# Interface.net
KiCad netlist of a schematic drawn in Altium Designer
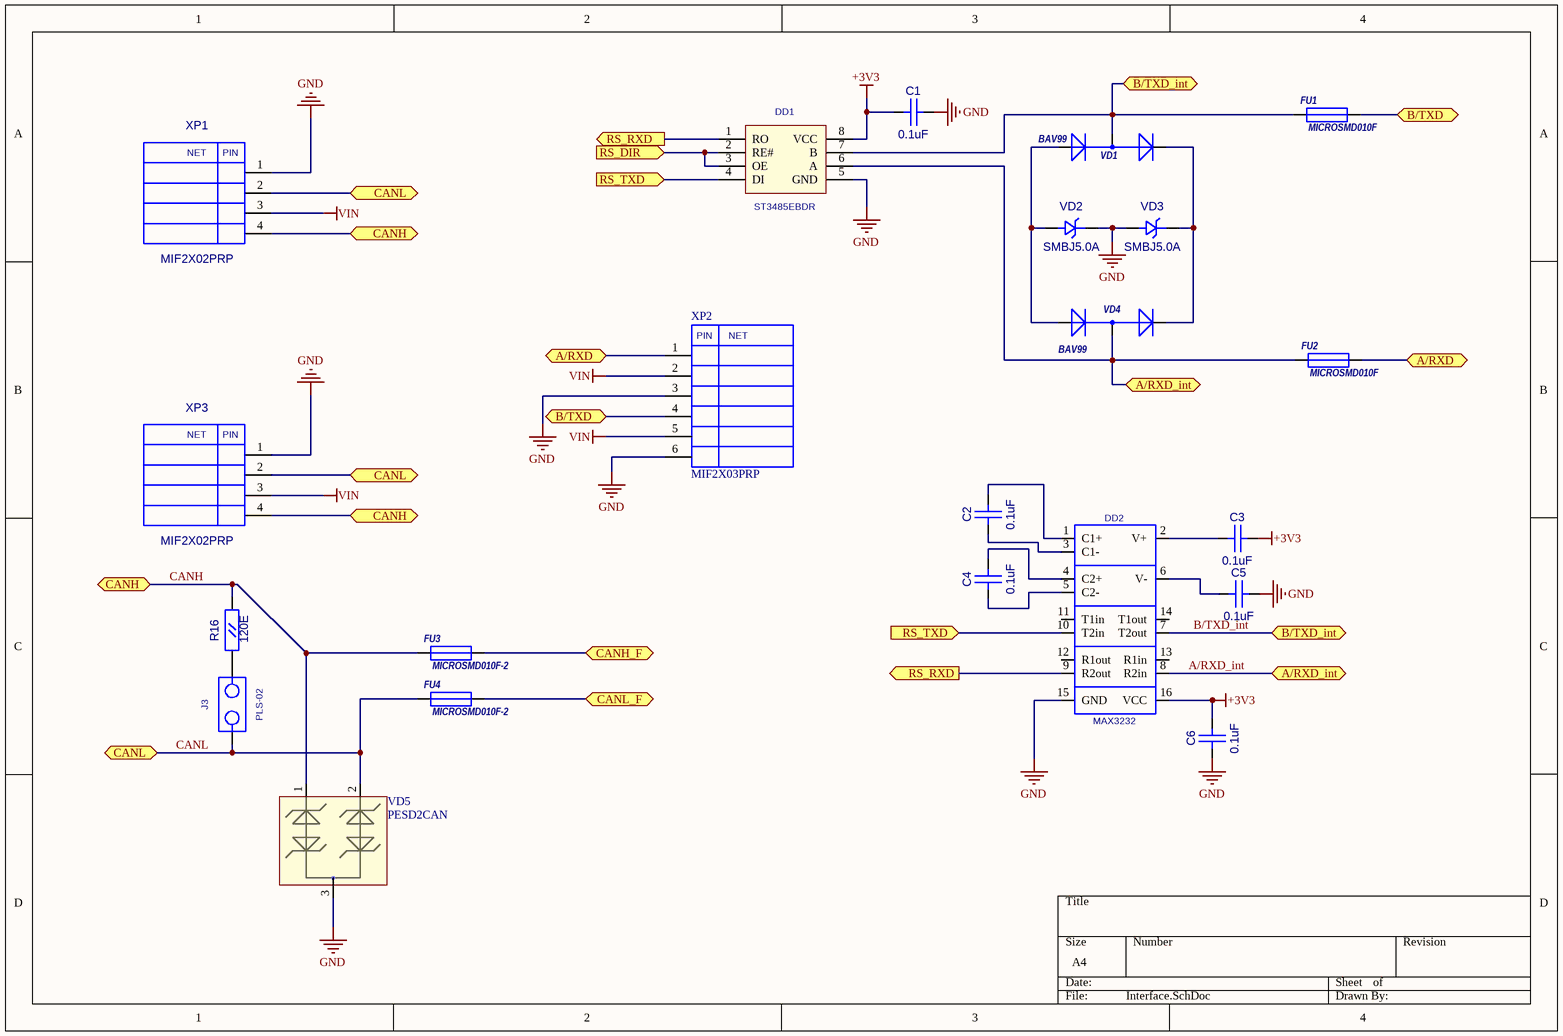
[diagram p0: Interface.SchDoc]

(export (version "E")
  (design (tool "Eeschema 10.0.6"))
  (components
    (comp (ref "C1")
      (value "0.1uF")
      (footprint "CC0603")
      (description "CC0603")
      (libsource (lib "gprs_modem_2") (part "CC0603"))
    )
    (comp (ref "C2")
      (value "0.1uF")
      (footprint "CC0603")
      (description "CC0603")
      (libsource (lib "gprs_modem_2") (part "CC0603"))
    )
    (comp (ref "C3")
      (value "0.1uF")
      (footprint "CC0603")
      (description "CC0603")
      (libsource (lib "gprs_modem_2") (part "CC0603"))
    )
    (comp (ref "C4")
      (value "0.1uF")
      (footprint "CC0603")
      (description "CC0603")
      (libsource (lib "gprs_modem_2") (part "CC0603"))
    )
    (comp (ref "C5")
      (value "0.1uF")
      (footprint "CC0603")
      (description "CC0603")
      (libsource (lib "gprs_modem_2") (part "CC0603"))
    )
    (comp (ref "C6")
      (value "0.1uF")
      (footprint "CC0603")
      (description "CC0603")
      (libsource (lib "gprs_modem_2") (part "CC0603"))
    )
    (comp (ref "DD1")
      (value "ST3485EBDR")
      (footprint "SO-8")
      (description "SP485")
      (libsource (lib "gprs_modem_2") (part "SP485"))
    )
    (comp (ref "DD2")
      (value "MAX3232")
      (footprint "SO16_M")
      (description "ST232BD/CD")
      (libsource (lib "gprs_modem_2") (part "ST232BD/CD"))
    )
    (comp (ref "FU1")
      (value "MICROSMD010F")
      (footprint "RC1210")
      (description "MICROSMD")
      (libsource (lib "gprs_modem_2") (part "MICROSMD"))
    )
    (comp (ref "FU2")
      (value "MICROSMD010F")
      (footprint "RC1210")
      (description "MICROSMD")
      (libsource (lib "gprs_modem_2") (part "MICROSMD"))
    )
    (comp (ref "FU3")
      (value "MICROSMD010F-2")
      (footprint "RC1210")
      (description "MICROSMD")
      (libsource (lib "gprs_modem_2") (part "MICROSMD"))
    )
    (comp (ref "FU4")
      (value "MICROSMD010F-2")
      (footprint "RC1210")
      (description "MICROSMD")
      (libsource (lib "gprs_modem_2") (part "MICROSMD"))
    )
    (comp (ref "J3") (value "PLS-02") (footprint "PLS-02") (libsource (lib "gprs_modem_2") (part "PLS-02")))
    (comp (ref "R16")
      (value "120E")
      (footprint "RC0805")
      (description "RC0805")
      (libsource (lib "gprs_modem_2") (part "RC0805"))
    )
    (comp (ref "VD1")
      (value "BAV99")
      (footprint "SOT-23(GSD)")
      (description "1.0 Ampere General Purpose Rectifier")
      (libsource (lib "gprs_modem_2") (part "BAV99"))
    )
    (comp (ref "VD2")
      (value "SMBJ5.0A")
      (footprint "SMB")
      (description "SMBJ")
      (libsource (lib "gprs_modem_2") (part "SMBJ"))
    )
    (comp (ref "VD3")
      (value "SMBJ5.0A")
      (footprint "SMB")
      (description "SMBJ")
      (libsource (lib "gprs_modem_2") (part "SMBJ"))
    )
    (comp (ref "VD4")
      (value "BAV99")
      (footprint "SOT-23(GSD)")
      (description "1.0 Ampere General Purpose Rectifier")
      (libsource (lib "gprs_modem_2") (part "BAV99"))
    )
    (comp (ref "VD5")
      (value "PESD2CAN")
      (footprint "SOT-23(123)")
      (description "TVS for CAN")
      (libsource (lib "gprs_modem_2") (part "PESD2CAN"))
    )
    (comp (ref "XP1")
      (value "MIF2X02PRP")
      (footprint "MIF2X02PRP")
      (libsource (lib "gprs_modem_2") (part "MIF2X02PRP"))
    )
    (comp (ref "XP2")
      (value "MIF2X03PRP")
      (footprint "MIF2X03PRP")
      (description "MIF2x03PRP")
      (libsource (lib "gprs_modem") (part "MIF2X03PRP"))
    )
    (comp (ref "XP3")
      (value "MIF2X02PRP")
      (footprint "MIF2X02PRP")
      (libsource (lib "gprs_modem_2") (part "MIF2X02PRP"))
    )
  )
  (nets
    (net (code "1") (name "+3V3") (class "Default")
      (node (ref "C1") (pin "1") (pinfunction "A_1") (pintype "passive"))
      (node (ref "C3") (pin "2") (pinfunction "B_2") (pintype "passive"))
      (node (ref "C6") (pin "2") (pinfunction "B_2") (pintype "passive"))
      (node (ref "DD1") (pin "8") (pinfunction "VCC_8") (pintype "passive"))
      (node (ref "DD2") (pin "16") (pinfunction "VCC_16") (pintype "passive"))
    )
    (net (code "2") (name "/A{slash}RXD") (class "Default")
      (node (ref "FU2") (pin "2") (pintype "passive"))
      (node (ref "XP2") (pin "1") (pinfunction "1_1") (pintype "passive"))
    )
    (net (code "3") (name "/A{slash}RXD_int") (class "Default")
      (node (ref "DD1") (pin "6") (pinfunction "A_6") (pintype "passive"))
      (node (ref "DD2") (pin "8") (pinfunction "R2in_8") (pintype "passive"))
      (node (ref "FU2") (pin "1") (pintype "passive"))
      (node (ref "VD4") (pin "3") (pinfunction "AK_3") (pintype "passive"))
    )
    (net (code "4") (name "/B{slash}TXD") (class "Default")
      (node (ref "FU1") (pin "2") (pintype "passive"))
      (node (ref "XP2") (pin "4") (pinfunction "4_4") (pintype "passive"))
    )
    (net (code "5") (name "/B{slash}TXD_int") (class "Default")
      (node (ref "DD1") (pin "7") (pinfunction "B_7") (pintype "passive"))
      (node (ref "DD2") (pin "7") (pinfunction "T2out_7") (pintype "passive"))
      (node (ref "FU1") (pin "1") (pintype "passive"))
      (node (ref "VD1") (pin "3") (pinfunction "AK_3") (pintype "passive"))
    )
    (net (code "6") (name "/CANH") (class "Default")
      (node (ref "FU3") (pin "1") (pintype "passive"))
      (node (ref "R16") (pin "2") (pinfunction "B_2") (pintype "passive"))
      (node (ref "VD5") (pin "1") (pinfunction "1_1") (pintype "passive"))
      (node (ref "XP1") (pin "4") (pinfunction "4_4") (pintype "passive"))
      (node (ref "XP3") (pin "4") (pinfunction "4_4") (pintype "passive"))
    )
    (net (code "7") (name "/CANH_F") (class "Default") (node (ref "FU3") (pin "2") (pintype "passive")))
    (net (code "8") (name "/CANL") (class "Default")
      (node (ref "FU4") (pin "1") (pintype "passive"))
      (node (ref "J3") (pin "1") (pintype "passive"))
      (node (ref "VD5") (pin "2") (pinfunction "2_2") (pintype "passive"))
      (node (ref "XP1") (pin "2") (pinfunction "2_2") (pintype "passive"))
      (node (ref "XP3") (pin "2") (pinfunction "2_2") (pintype "passive"))
    )
    (net (code "9") (name "/CANL_F") (class "Default") (node (ref "FU4") (pin "2") (pintype "passive")))
    (net (code "10") (name "/RS_DIR") (class "Default")
      (node (ref "DD1") (pin "2") (pinfunction "RE#_2") (pintype "passive"))
      (node (ref "DD1") (pin "3") (pinfunction "OE_3") (pintype "passive"))
    )
    (net (code "11") (name "/RS_RXD") (class "Default")
      (node (ref "DD1") (pin "1") (pinfunction "RO_1") (pintype "passive"))
      (node (ref "DD2") (pin "9") (pinfunction "R2out_9") (pintype "passive"))
    )
    (net (code "12") (name "/RS_TXD") (class "Default")
      (node (ref "DD1") (pin "4") (pinfunction "DI_4") (pintype "passive"))
      (node (ref "DD2") (pin "10") (pinfunction "T2in_10") (pintype "passive"))
    )
    (net (code "13") (name "GND") (class "Default")
      (node (ref "C1") (pin "2") (pinfunction "B_2") (pintype "passive"))
      (node (ref "C5") (pin "2") (pinfunction "B_2") (pintype "passive"))
      (node (ref "C6") (pin "1") (pinfunction "A_1") (pintype "passive"))
      (node (ref "DD1") (pin "5") (pinfunction "GND_5") (pintype "passive"))
      (node (ref "DD2") (pin "15") (pinfunction "GND_15") (pintype "passive"))
      (node (ref "VD2") (pin "2") (pinfunction "K_2") (pintype "passive"))
      (node (ref "VD3") (pin "1") (pinfunction "A_1") (pintype "passive"))
      (node (ref "VD5") (pin "3") (pinfunction "3_3") (pintype "passive"))
      (node (ref "XP1") (pin "1") (pinfunction "1_1") (pintype "passive"))
      (node (ref "XP2") (pin "3") (pinfunction "3_3") (pintype "passive"))
      (node (ref "XP2") (pin "6") (pinfunction "6_6") (pintype "passive"))
      (node (ref "XP3") (pin "1") (pinfunction "1_1") (pintype "passive"))
    )
    (net (code "14") (name "Net-(C2-A)") (class "Default")
      (node (ref "C2") (pin "1") (pinfunction "A_1") (pintype "passive"))
      (node (ref "DD2") (pin "3") (pinfunction "C1-_3") (pintype "passive"))
    )
    (net (code "15") (name "Net-(C2-B)") (class "Default")
      (node (ref "C2") (pin "2") (pinfunction "B_2") (pintype "passive"))
      (node (ref "DD2") (pin "1") (pinfunction "C1+_1") (pintype "passive"))
    )
    (net (code "16") (name "Net-(C3-A)") (class "Default")
      (node (ref "C3") (pin "1") (pinfunction "A_1") (pintype "passive"))
      (node (ref "DD2") (pin "2") (pinfunction "V+_2") (pintype "passive"))
    )
    (net (code "17") (name "Net-(C4-A)") (class "Default")
      (node (ref "C4") (pin "1") (pinfunction "A_1") (pintype "passive"))
      (node (ref "DD2") (pin "5") (pinfunction "C2-_5") (pintype "passive"))
    )
    (net (code "18") (name "Net-(C4-B)") (class "Default")
      (node (ref "C4") (pin "2") (pinfunction "B_2") (pintype "passive"))
      (node (ref "DD2") (pin "4") (pinfunction "C2+_4") (pintype "passive"))
    )
    (net (code "19") (name "Net-(C5-A)") (class "Default")
      (node (ref "C5") (pin "1") (pinfunction "A_1") (pintype "passive"))
      (node (ref "DD2") (pin "6") (pinfunction "V-_6") (pintype "passive"))
    )
    (net (code "20") (name "Net-(R16-A)") (class "Default")
      (node (ref "J3") (pin "2") (pintype "passive"))
      (node (ref "R16") (pin "1") (pinfunction "A_1") (pintype "passive"))
    )
    (net (code "21") (name "Net-(VD1-A)") (class "Default")
      (node (ref "VD1") (pin "1") (pinfunction "A_1") (pintype "passive"))
      (node (ref "VD2") (pin "1") (pinfunction "A_1") (pintype "passive"))
      (node (ref "VD4") (pin "1") (pinfunction "A_1") (pintype "passive"))
    )
    (net (code "22") (name "Net-(VD1-K)") (class "Default")
      (node (ref "VD1") (pin "2") (pinfunction "K_2") (pintype "passive"))
      (node (ref "VD3") (pin "2") (pinfunction "K_2") (pintype "passive"))
      (node (ref "VD4") (pin "2") (pinfunction "K_2") (pintype "passive"))
    )
    (net (code "23") (name "VIN") (class "Default")
      (node (ref "XP1") (pin "3") (pinfunction "3_3") (pintype "passive"))
      (node (ref "XP2") (pin "2") (pinfunction "2_2") (pintype "passive"))
      (node (ref "XP2") (pin "5") (pinfunction "5_5") (pintype "passive"))
      (node (ref "XP3") (pin "3") (pinfunction "3_3") (pintype "passive"))
    )
    (net (code "24") (name "unconnected-(DD2-R1in-Pad13)") (class "Default")
      (node (ref "DD2") (pin "13") (pinfunction "R1in_13") (pintype "passive"))
    )
    (net (code "25") (name "unconnected-(DD2-R1out-Pad12)") (class "Default")
      (node (ref "DD2") (pin "12") (pinfunction "R1out_12") (pintype "passive"))
    )
    (net (code "26") (name "unconnected-(DD2-T1in-Pad11)") (class "Default")
      (node (ref "DD2") (pin "11") (pinfunction "T1in_11") (pintype "passive"))
    )
    (net (code "27") (name "unconnected-(DD2-T1out-Pad14)") (class "Default")
      (node (ref "DD2") (pin "14") (pinfunction "T1out_14") (pintype "passive"))
    )
  )
)
